# demo_dermis_chip1_package.net
KiCad netlist of a schematic drawn in Altium Designer
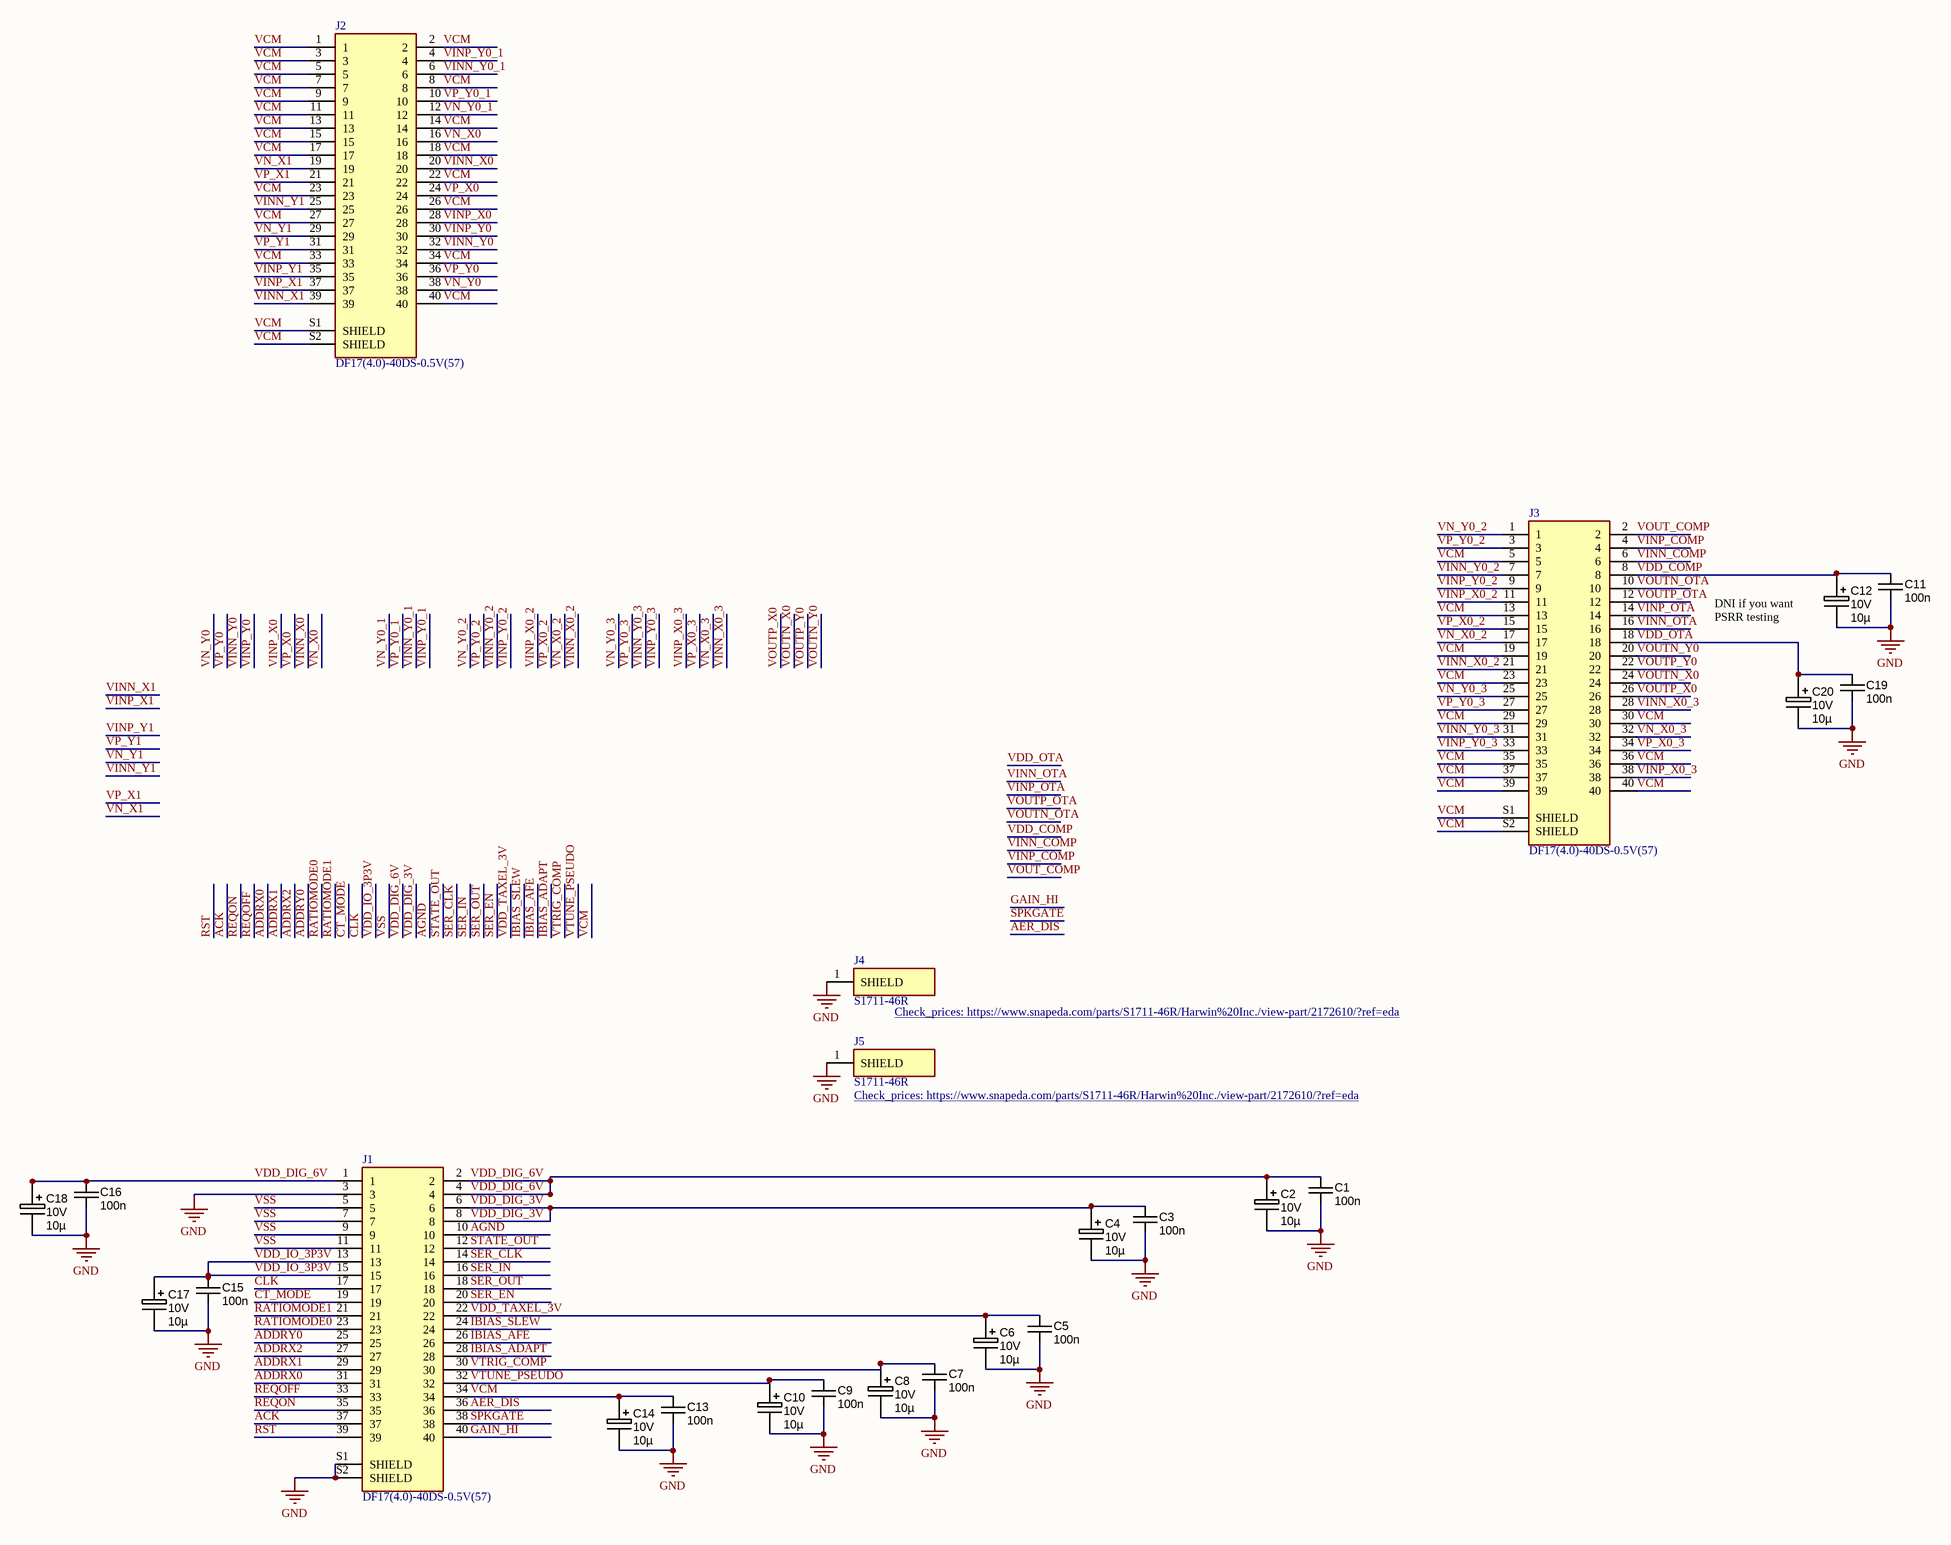
[diagram p0: demo_dermis_chip1_package.SchDoc]

(export (version "E")
  (design (tool "Eeschema 10.0.6"))
  (components
    (comp (ref "C1")
      (value "100n")
      (footprint "CAPC1608N")
      (description "Capacitor SMD Cer 100nF 10% 50V X7R 0603")
      (fields (field (name "TOLERANCE") "±10%") (field (name "Comment") "approved sub OK"))
      (libsource (lib "PBL - Capacitors") (part "CAPC_100n_0603"))
    )
    (comp (ref "C2")
      (value "10µ")
      (footprint "CAPMP2012X150USR")
      (description "Capacitor SMD Tantalum 10uF 20% 10V 0805")
      (fields (field (name "TOLERANCE") "±20%") (field (name "RATINGS") "10V"))
      (libsource (lib "PBL - Capacitors") (part "CAPT_10u_0805_10V"))
    )
    (comp (ref "C3")
      (value "100n")
      (footprint "CAPC1608N")
      (description "Capacitor SMD Cer 100nF 10% 50V X7R 0603")
      (fields (field (name "TOLERANCE") "±10%") (field (name "Comment") "approved sub OK"))
      (libsource (lib "PBL - Capacitors") (part "CAPC_100n_0603"))
    )
    (comp (ref "C4")
      (value "10µ")
      (footprint "CAPMP2012X150USR")
      (description "Capacitor SMD Tantalum 10uF 20% 10V 0805")
      (fields (field (name "TOLERANCE") "±20%") (field (name "RATINGS") "10V"))
      (libsource (lib "PBL - Capacitors") (part "CAPT_10u_0805_10V"))
    )
    (comp (ref "C5")
      (value "100n")
      (footprint "CAPC1608N")
      (description "Capacitor SMD Cer 100nF 10% 50V X7R 0603")
      (fields (field (name "TOLERANCE") "±10%") (field (name "Comment") "approved sub OK"))
      (libsource (lib "PBL - Capacitors") (part "CAPC_100n_0603"))
    )
    (comp (ref "C6")
      (value "10µ")
      (footprint "CAPMP2012X150USR")
      (description "Capacitor SMD Tantalum 10uF 20% 10V 0805")
      (fields (field (name "TOLERANCE") "±20%") (field (name "RATINGS") "10V"))
      (libsource (lib "PBL - Capacitors") (part "CAPT_10u_0805_10V"))
    )
    (comp (ref "C7")
      (value "100n")
      (footprint "CAPC1608N")
      (description "Capacitor SMD Cer 100nF 10% 50V X7R 0603")
      (fields (field (name "TOLERANCE") "±10%") (field (name "Comment") "approved sub OK"))
      (libsource (lib "PBL - Capacitors") (part "CAPC_100n_0603"))
    )
    (comp (ref "C8")
      (value "10µ")
      (footprint "CAPMP2012X150USR")
      (description "Capacitor SMD Tantalum 10uF 20% 10V 0805")
      (fields (field (name "TOLERANCE") "±20%") (field (name "RATINGS") "10V"))
      (libsource (lib "PBL - Capacitors") (part "CAPT_10u_0805_10V"))
    )
    (comp (ref "C9")
      (value "100n")
      (footprint "CAPC1608N")
      (description "Capacitor SMD Cer 100nF 10% 50V X7R 0603")
      (fields (field (name "TOLERANCE") "±10%") (field (name "Comment") "approved sub OK"))
      (libsource (lib "PBL - Capacitors") (part "CAPC_100n_0603"))
    )
    (comp (ref "C10")
      (value "10µ")
      (footprint "CAPMP2012X150USR")
      (description "Capacitor SMD Tantalum 10uF 20% 10V 0805")
      (fields (field (name "TOLERANCE") "±20%") (field (name "RATINGS") "10V"))
      (libsource (lib "PBL - Capacitors") (part "CAPT_10u_0805_10V"))
    )
    (comp (ref "C11")
      (value "100n")
      (footprint "CAPC1608N")
      (description "Capacitor SMD Cer 100nF 10% 50V X7R 0603")
      (fields (field (name "TOLERANCE") "±10%") (field (name "Comment") "approved sub OK"))
      (libsource (lib "PBL - Capacitors") (part "CAPC_100n_0603"))
    )
    (comp (ref "C12")
      (value "10µ")
      (footprint "CAPMP2012X150USR")
      (description "Capacitor SMD Tantalum 10uF 20% 10V 0805")
      (fields (field (name "TOLERANCE") "±20%") (field (name "RATINGS") "10V"))
      (libsource (lib "PBL - Capacitors") (part "CAPT_10u_0805_10V"))
    )
    (comp (ref "C13")
      (value "100n")
      (footprint "CAPC1608N")
      (description "Capacitor SMD Cer 100nF 10% 50V X7R 0603")
      (fields (field (name "TOLERANCE") "±10%") (field (name "Comment") "approved sub OK"))
      (libsource (lib "PBL - Capacitors") (part "CAPC_100n_0603"))
    )
    (comp (ref "C14")
      (value "10µ")
      (footprint "CAPMP2012X150USR")
      (description "Capacitor SMD Tantalum 10uF 20% 10V 0805")
      (fields (field (name "TOLERANCE") "±20%") (field (name "RATINGS") "10V"))
      (libsource (lib "PBL - Capacitors") (part "CAPT_10u_0805_10V"))
    )
    (comp (ref "C15")
      (value "100n")
      (footprint "CAPC1608N")
      (description "Capacitor SMD Cer 100nF 10% 50V X7R 0603")
      (fields (field (name "TOLERANCE") "±10%") (field (name "Comment") "approved sub OK"))
      (libsource (lib "PBL - Capacitors") (part "CAPC_100n_0603"))
    )
    (comp (ref "C16")
      (value "100n")
      (footprint "CAPC1608N")
      (description "Capacitor SMD Cer 100nF 10% 50V X7R 0603")
      (fields (field (name "TOLERANCE") "±10%") (field (name "Comment") "approved sub OK"))
      (libsource (lib "PBL - Capacitors") (part "CAPC_100n_0603"))
    )
    (comp (ref "C17")
      (value "10µ")
      (footprint "CAPMP2012X150USR")
      (description "Capacitor SMD Tantalum 10uF 20% 10V 0805")
      (fields (field (name "TOLERANCE") "±20%") (field (name "RATINGS") "10V"))
      (libsource (lib "PBL - Capacitors") (part "CAPT_10u_0805_10V"))
    )
    (comp (ref "C18")
      (value "10µ")
      (footprint "CAPMP2012X150USR")
      (description "Capacitor SMD Tantalum 10uF 20% 10V 0805")
      (fields (field (name "TOLERANCE") "±20%") (field (name "RATINGS") "10V"))
      (libsource (lib "PBL - Capacitors") (part "CAPT_10u_0805_10V"))
    )
    (comp (ref "C19")
      (value "100n")
      (footprint "CAPC1608N")
      (description "Capacitor SMD Cer 100nF 10% 50V X7R 0603")
      (fields (field (name "TOLERANCE") "±10%") (field (name "Comment") "approved sub OK"))
      (libsource (lib "PBL - Capacitors") (part "CAPC_100n_0603"))
    )
    (comp (ref "C20")
      (value "10µ")
      (footprint "CAPMP2012X150USR")
      (description "Capacitor SMD Tantalum 10uF 20% 10V 0805")
      (fields (field (name "TOLERANCE") "±20%") (field (name "RATINGS") "10V"))
      (libsource (lib "PBL - Capacitors") (part "CAPT_10u_0805_10V"))
    )
    (comp (ref "J1")
      (value "DF17(4.0)-40DS-0.5V(57)")
      (footprint "HRS_DF17(4.0)-40DS-0.5V(57)")
      (fields (field (name "MF") "Hirose Electric"))
      (libsource (lib "DF17(4.0)-40DS-0.5V(57)") (part "DF17(4.0)-40DS-0.5V(57)"))
    )
    (comp (ref "J2")
      (value "DF17(4.0)-40DS-0.5V(57)")
      (footprint "HRS_DF17(4.0)-40DS-0.5V(57)")
      (fields (field (name "MF") "Hirose Electric"))
      (libsource (lib "DF17(4.0)-40DS-0.5V(57)") (part "DF17(4.0)-40DS-0.5V(57)"))
    )
    (comp (ref "J3")
      (value "DF17(4.0)-40DS-0.5V(57)")
      (footprint "HRS_DF17(4.0)-40DS-0.5V(57)")
      (fields (field (name "MF") "Hirose Electric"))
      (libsource (lib "DF17(4.0)-40DS-0.5V(57)") (part "DF17(4.0)-40DS-0.5V(57)"))
    )
    (comp (ref "J4")
      (value "S1711-46R")
      (footprint "HARWIN_S1711-46R")
      (description "RFI SHIELD CLIP TIN SMD")
      (fields
        (field (name "MF") "Harwin Inc.")
        (field (name "CHECK_PRICES") "https://www.snapeda.com/parts/S1711-46R/Harwin%20Inc./view-part/2172610/?ref=eda")
      )
      (libsource (lib "S1711-46R") (part "S1711-46R"))
    )
    (comp (ref "J5")
      (value "S1711-46R")
      (footprint "HARWIN_S1711-46R")
      (description "RFI SHIELD CLIP TIN SMD")
      (fields
        (field (name "MF") "Harwin Inc.")
        (field (name "CHECK_PRICES") "https://www.snapeda.com/parts/S1711-46R/Harwin%20Inc./view-part/2172610/?ref=eda")
      )
      (libsource (lib "S1711-46R") (part "S1711-46R"))
    )
  )
  (nets
    (net (code "1") (name "/ACK") (class "Default")
      (node (ref "J1") (pin "37") (pinfunction "37_37") (pintype "passive"))
    )
    (net (code "2") (name "/ADDRX0") (class "Default")
      (node (ref "J1") (pin "31") (pinfunction "31_31") (pintype "passive"))
    )
    (net (code "3") (name "/ADDRX1") (class "Default")
      (node (ref "J1") (pin "29") (pinfunction "29_29") (pintype "passive"))
    )
    (net (code "4") (name "/ADDRX2") (class "Default")
      (node (ref "J1") (pin "27") (pinfunction "27_27") (pintype "passive"))
    )
    (net (code "5") (name "/ADDRY0") (class "Default")
      (node (ref "J1") (pin "25") (pinfunction "25_25") (pintype "passive"))
    )
    (net (code "6") (name "/AER_DIS") (class "Default")
      (node (ref "J1") (pin "36") (pinfunction "36_36") (pintype "passive"))
    )
    (net (code "7") (name "/AGND") (class "Default")
      (node (ref "J1") (pin "10") (pinfunction "10_10") (pintype "passive"))
    )
    (net (code "8") (name "/CLK") (class "Default")
      (node (ref "J1") (pin "17") (pinfunction "17_17") (pintype "passive"))
    )
    (net (code "9") (name "/CT_MODE") (class "Default")
      (node (ref "J1") (pin "19") (pinfunction "19_19") (pintype "passive"))
    )
    (net (code "10") (name "/GAIN_HI") (class "Default")
      (node (ref "J1") (pin "40") (pinfunction "40_40") (pintype "passive"))
    )
    (net (code "11") (name "/IBIAS_ADAPT") (class "Default")
      (node (ref "J1") (pin "28") (pinfunction "28_28") (pintype "passive"))
    )
    (net (code "12") (name "/IBIAS_AFE") (class "Default")
      (node (ref "J1") (pin "26") (pinfunction "26_26") (pintype "passive"))
    )
    (net (code "13") (name "/IBIAS_SLEW") (class "Default")
      (node (ref "J1") (pin "24") (pinfunction "24_24") (pintype "passive"))
    )
    (net (code "14") (name "/RATIOMODE0") (class "Default")
      (node (ref "J1") (pin "23") (pinfunction "23_23") (pintype "passive"))
    )
    (net (code "15") (name "/RATIOMODE1") (class "Default")
      (node (ref "J1") (pin "21") (pinfunction "21_21") (pintype "passive"))
    )
    (net (code "16") (name "/REQOFF") (class "Default")
      (node (ref "J1") (pin "33") (pinfunction "33_33") (pintype "passive"))
    )
    (net (code "17") (name "/REQON") (class "Default")
      (node (ref "J1") (pin "35") (pinfunction "35_35") (pintype "passive"))
    )
    (net (code "18") (name "/RST") (class "Default")
      (node (ref "J1") (pin "39") (pinfunction "39_39") (pintype "passive"))
    )
    (net (code "19") (name "/SER_CLK") (class "Default")
      (node (ref "J1") (pin "14") (pinfunction "14_14") (pintype "passive"))
    )
    (net (code "20") (name "/SER_EN") (class "Default")
      (node (ref "J1") (pin "20") (pinfunction "20_20") (pintype "passive"))
    )
    (net (code "21") (name "/SER_IN") (class "Default")
      (node (ref "J1") (pin "16") (pinfunction "16_16") (pintype "passive"))
    )
    (net (code "22") (name "/SER_OUT") (class "Default")
      (node (ref "J1") (pin "18") (pinfunction "18_18") (pintype "passive"))
    )
    (net (code "23") (name "/SPKGATE") (class "Default")
      (node (ref "J1") (pin "38") (pinfunction "38_38") (pintype "passive"))
    )
    (net (code "24") (name "/STATE_OUT") (class "Default")
      (node (ref "J1") (pin "12") (pinfunction "12_12") (pintype "passive"))
    )
    (net (code "25") (name "/VCM") (class "Default")
      (node (ref "C13") (pin "1") (pintype "passive"))
      (node (ref "C14") (pin "1") (pintype "passive"))
      (node (ref "J1") (pin "34") (pinfunction "34_34") (pintype "passive"))
      (node (ref "J2") (pin "1") (pinfunction "1_1") (pintype "passive"))
      (node (ref "J2") (pin "11") (pinfunction "11_11") (pintype "passive"))
      (node (ref "J2") (pin "13") (pinfunction "13_13") (pintype "passive"))
      (node (ref "J2") (pin "14") (pinfunction "14_14") (pintype "passive"))
      (node (ref "J2") (pin "15") (pinfunction "15_15") (pintype "passive"))
      (node (ref "J2") (pin "17") (pinfunction "17_17") (pintype "passive"))
      (node (ref "J2") (pin "18") (pinfunction "18_18") (pintype "passive"))
      (node (ref "J2") (pin "2") (pinfunction "2_2") (pintype "passive"))
      (node (ref "J2") (pin "22") (pinfunction "22_22") (pintype "passive"))
      (node (ref "J2") (pin "23") (pinfunction "23_23") (pintype "passive"))
      (node (ref "J2") (pin "26") (pinfunction "26_26") (pintype "passive"))
      (node (ref "J2") (pin "27") (pinfunction "27_27") (pintype "passive"))
      (node (ref "J2") (pin "3") (pinfunction "3_3") (pintype "passive"))
      (node (ref "J2") (pin "33") (pinfunction "33_33") (pintype "passive"))
      (node (ref "J2") (pin "34") (pinfunction "34_34") (pintype "passive"))
      (node (ref "J2") (pin "40") (pinfunction "40_40") (pintype "passive"))
      (node (ref "J2") (pin "5") (pinfunction "5_5") (pintype "passive"))
      (node (ref "J2") (pin "7") (pinfunction "7_7") (pintype "passive"))
      (node (ref "J2") (pin "8") (pinfunction "8_8") (pintype "passive"))
      (node (ref "J2") (pin "9") (pinfunction "9_9") (pintype "passive"))
      (node (ref "J2") (pin "S1") (pinfunction "SHIELD_S1") (pintype "passive"))
      (node (ref "J2") (pin "S2") (pinfunction "SHIELD_S2") (pintype "passive"))
      (node (ref "J3") (pin "13") (pinfunction "13_13") (pintype "passive"))
      (node (ref "J3") (pin "19") (pinfunction "19_19") (pintype "passive"))
      (node (ref "J3") (pin "23") (pinfunction "23_23") (pintype "passive"))
      (node (ref "J3") (pin "29") (pinfunction "29_29") (pintype "passive"))
      (node (ref "J3") (pin "30") (pinfunction "30_30") (pintype "passive"))
      (node (ref "J3") (pin "35") (pinfunction "35_35") (pintype "passive"))
      (node (ref "J3") (pin "36") (pinfunction "36_36") (pintype "passive"))
      (node (ref "J3") (pin "37") (pinfunction "37_37") (pintype "passive"))
      (node (ref "J3") (pin "39") (pinfunction "39_39") (pintype "passive"))
      (node (ref "J3") (pin "40") (pinfunction "40_40") (pintype "passive"))
      (node (ref "J3") (pin "5") (pinfunction "5_5") (pintype "passive"))
      (node (ref "J3") (pin "S1") (pinfunction "SHIELD_S1") (pintype "passive"))
      (node (ref "J3") (pin "S2") (pinfunction "SHIELD_S2") (pintype "passive"))
    )
    (net (code "26") (name "/VDD_COMP") (class "Default")
      (node (ref "C11") (pin "1") (pintype "passive"))
      (node (ref "C12") (pin "1") (pintype "passive"))
      (node (ref "J3") (pin "8") (pinfunction "8_8") (pintype "passive"))
    )
    (net (code "27") (name "/VDD_DIG_3V") (class "Default")
      (node (ref "C3") (pin "1") (pintype "passive"))
      (node (ref "C4") (pin "1") (pintype "passive"))
      (node (ref "J1") (pin "6") (pinfunction "6_6") (pintype "passive"))
      (node (ref "J1") (pin "8") (pinfunction "8_8") (pintype "passive"))
    )
    (net (code "28") (name "/VDD_DIG_6V") (class "Default")
      (node (ref "C1") (pin "1") (pintype "passive"))
      (node (ref "C16") (pin "1") (pintype "passive"))
      (node (ref "C18") (pin "1") (pintype "passive"))
      (node (ref "C2") (pin "1") (pintype "passive"))
      (node (ref "J1") (pin "1") (pinfunction "1_1") (pintype "passive"))
      (node (ref "J1") (pin "2") (pinfunction "2_2") (pintype "passive"))
      (node (ref "J1") (pin "4") (pinfunction "4_4") (pintype "passive"))
    )
    (net (code "29") (name "/VDD_IO_3P3V") (class "Default")
      (node (ref "C15") (pin "1") (pintype "passive"))
      (node (ref "C17") (pin "1") (pintype "passive"))
      (node (ref "J1") (pin "13") (pinfunction "13_13") (pintype "passive"))
      (node (ref "J1") (pin "15") (pinfunction "15_15") (pintype "passive"))
    )
    (net (code "30") (name "/VDD_OTA") (class "Default")
      (node (ref "C19") (pin "1") (pintype "passive"))
      (node (ref "C20") (pin "1") (pintype "passive"))
      (node (ref "J3") (pin "18") (pinfunction "18_18") (pintype "passive"))
    )
    (net (code "31") (name "/VDD_TAXEL_3V") (class "Default")
      (node (ref "C5") (pin "1") (pintype "passive"))
      (node (ref "C6") (pin "1") (pintype "passive"))
      (node (ref "J1") (pin "22") (pinfunction "22_22") (pintype "passive"))
    )
    (net (code "32") (name "/VINN_COMP") (class "Default")
      (node (ref "J3") (pin "6") (pinfunction "6_6") (pintype "passive"))
    )
    (net (code "33") (name "/VINN_OTA") (class "Default")
      (node (ref "J3") (pin "16") (pinfunction "16_16") (pintype "passive"))
    )
    (net (code "34") (name "/VINN_X0") (class "Default")
      (node (ref "J2") (pin "20") (pinfunction "20_20") (pintype "passive"))
    )
    (net (code "35") (name "/VINN_X0_2") (class "Default")
      (node (ref "J3") (pin "21") (pinfunction "21_21") (pintype "passive"))
    )
    (net (code "36") (name "/VINN_X0_3") (class "Default")
      (node (ref "J3") (pin "28") (pinfunction "28_28") (pintype "passive"))
    )
    (net (code "37") (name "/VINN_X1") (class "Default")
      (node (ref "J2") (pin "39") (pinfunction "39_39") (pintype "passive"))
    )
    (net (code "38") (name "/VINN_Y0") (class "Default")
      (node (ref "J2") (pin "32") (pinfunction "32_32") (pintype "passive"))
    )
    (net (code "39") (name "/VINN_Y0_1") (class "Default")
      (node (ref "J2") (pin "6") (pinfunction "6_6") (pintype "passive"))
    )
    (net (code "40") (name "/VINN_Y0_2") (class "Default")
      (node (ref "J3") (pin "7") (pinfunction "7_7") (pintype "passive"))
    )
    (net (code "41") (name "/VINN_Y0_3") (class "Default")
      (node (ref "J3") (pin "31") (pinfunction "31_31") (pintype "passive"))
    )
    (net (code "42") (name "/VINN_Y1") (class "Default")
      (node (ref "J2") (pin "25") (pinfunction "25_25") (pintype "passive"))
    )
    (net (code "43") (name "/VINP_COMP") (class "Default")
      (node (ref "J3") (pin "4") (pinfunction "4_4") (pintype "passive"))
    )
    (net (code "44") (name "/VINP_OTA") (class "Default")
      (node (ref "J3") (pin "14") (pinfunction "14_14") (pintype "passive"))
    )
    (net (code "45") (name "/VINP_X0") (class "Default")
      (node (ref "J2") (pin "28") (pinfunction "28_28") (pintype "passive"))
    )
    (net (code "46") (name "/VINP_X0_2") (class "Default")
      (node (ref "J3") (pin "11") (pinfunction "11_11") (pintype "passive"))
    )
    (net (code "47") (name "/VINP_X0_3") (class "Default")
      (node (ref "J3") (pin "38") (pinfunction "38_38") (pintype "passive"))
    )
    (net (code "48") (name "/VINP_X1") (class "Default")
      (node (ref "J2") (pin "37") (pinfunction "37_37") (pintype "passive"))
    )
    (net (code "49") (name "/VINP_Y0") (class "Default")
      (node (ref "J2") (pin "30") (pinfunction "30_30") (pintype "passive"))
    )
    (net (code "50") (name "/VINP_Y0_1") (class "Default")
      (node (ref "J2") (pin "4") (pinfunction "4_4") (pintype "passive"))
    )
    (net (code "51") (name "/VINP_Y0_2") (class "Default")
      (node (ref "J3") (pin "9") (pinfunction "9_9") (pintype "passive"))
    )
    (net (code "52") (name "/VINP_Y0_3") (class "Default")
      (node (ref "J3") (pin "33") (pinfunction "33_33") (pintype "passive"))
    )
    (net (code "53") (name "/VINP_Y1") (class "Default")
      (node (ref "J2") (pin "35") (pinfunction "35_35") (pintype "passive"))
    )
    (net (code "54") (name "/VN_X0") (class "Default")
      (node (ref "J2") (pin "16") (pinfunction "16_16") (pintype "passive"))
    )
    (net (code "55") (name "/VN_X0_2") (class "Default")
      (node (ref "J3") (pin "17") (pinfunction "17_17") (pintype "passive"))
    )
    (net (code "56") (name "/VN_X0_3") (class "Default")
      (node (ref "J3") (pin "32") (pinfunction "32_32") (pintype "passive"))
    )
    (net (code "57") (name "/VN_X1") (class "Default")
      (node (ref "J2") (pin "19") (pinfunction "19_19") (pintype "passive"))
    )
    (net (code "58") (name "/VN_Y0") (class "Default")
      (node (ref "J2") (pin "38") (pinfunction "38_38") (pintype "passive"))
    )
    (net (code "59") (name "/VN_Y0_1") (class "Default")
      (node (ref "J2") (pin "12") (pinfunction "12_12") (pintype "passive"))
    )
    (net (code "60") (name "/VN_Y0_2") (class "Default")
      (node (ref "J3") (pin "1") (pinfunction "1_1") (pintype "passive"))
    )
    (net (code "61") (name "/VN_Y0_3") (class "Default")
      (node (ref "J3") (pin "25") (pinfunction "25_25") (pintype "passive"))
    )
    (net (code "62") (name "/VN_Y1") (class "Default")
      (node (ref "J2") (pin "29") (pinfunction "29_29") (pintype "passive"))
    )
    (net (code "63") (name "/VOUTN_OTA") (class "Default")
      (node (ref "J3") (pin "10") (pinfunction "10_10") (pintype "passive"))
    )
    (net (code "64") (name "/VOUTN_X0") (class "Default")
      (node (ref "J3") (pin "24") (pinfunction "24_24") (pintype "passive"))
    )
    (net (code "65") (name "/VOUTN_Y0") (class "Default")
      (node (ref "J3") (pin "20") (pinfunction "20_20") (pintype "passive"))
    )
    (net (code "66") (name "/VOUTP_OTA") (class "Default")
      (node (ref "J3") (pin "12") (pinfunction "12_12") (pintype "passive"))
    )
    (net (code "67") (name "/VOUTP_X0") (class "Default")
      (node (ref "J3") (pin "26") (pinfunction "26_26") (pintype "passive"))
    )
    (net (code "68") (name "/VOUTP_Y0") (class "Default")
      (node (ref "J3") (pin "22") (pinfunction "22_22") (pintype "passive"))
    )
    (net (code "69") (name "/VOUT_COMP") (class "Default")
      (node (ref "J3") (pin "2") (pinfunction "2_2") (pintype "passive"))
    )
    (net (code "70") (name "/VP_X0") (class "Default")
      (node (ref "J2") (pin "24") (pinfunction "24_24") (pintype "passive"))
    )
    (net (code "71") (name "/VP_X0_2") (class "Default")
      (node (ref "J3") (pin "15") (pinfunction "15_15") (pintype "passive"))
    )
    (net (code "72") (name "/VP_X0_3") (class "Default")
      (node (ref "J3") (pin "34") (pinfunction "34_34") (pintype "passive"))
    )
    (net (code "73") (name "/VP_X1") (class "Default")
      (node (ref "J2") (pin "21") (pinfunction "21_21") (pintype "passive"))
    )
    (net (code "74") (name "/VP_Y0") (class "Default")
      (node (ref "J2") (pin "36") (pinfunction "36_36") (pintype "passive"))
    )
    (net (code "75") (name "/VP_Y0_1") (class "Default")
      (node (ref "J2") (pin "10") (pinfunction "10_10") (pintype "passive"))
    )
    (net (code "76") (name "/VP_Y0_2") (class "Default")
      (node (ref "J3") (pin "3") (pinfunction "3_3") (pintype "passive"))
    )
    (net (code "77") (name "/VP_Y0_3") (class "Default")
      (node (ref "J3") (pin "27") (pinfunction "27_27") (pintype "passive"))
    )
    (net (code "78") (name "/VP_Y1") (class "Default")
      (node (ref "J2") (pin "31") (pinfunction "31_31") (pintype "passive"))
    )
    (net (code "79") (name "/VSS") (class "Default")
      (node (ref "J1") (pin "11") (pinfunction "11_11") (pintype "passive"))
      (node (ref "J1") (pin "5") (pinfunction "5_5") (pintype "passive"))
      (node (ref "J1") (pin "7") (pinfunction "7_7") (pintype "passive"))
      (node (ref "J1") (pin "9") (pinfunction "9_9") (pintype "passive"))
    )
    (net (code "80") (name "/VTRIG_COMP") (class "Default")
      (node (ref "C7") (pin "1") (pintype "passive"))
      (node (ref "C8") (pin "1") (pintype "passive"))
      (node (ref "J1") (pin "30") (pinfunction "30_30") (pintype "passive"))
    )
    (net (code "81") (name "/VTUNE_PSEUDO") (class "Default")
      (node (ref "C10") (pin "1") (pintype "passive"))
      (node (ref "C9") (pin "1") (pintype "passive"))
      (node (ref "J1") (pin "32") (pinfunction "32_32") (pintype "passive"))
    )
    (net (code "82") (name "GND") (class "Default")
      (node (ref "C1") (pin "2") (pintype "passive"))
      (node (ref "C10") (pin "2") (pintype "passive"))
      (node (ref "C11") (pin "2") (pintype "passive"))
      (node (ref "C12") (pin "2") (pintype "passive"))
      (node (ref "C13") (pin "2") (pintype "passive"))
      (node (ref "C14") (pin "2") (pintype "passive"))
      (node (ref "C15") (pin "2") (pintype "passive"))
      (node (ref "C16") (pin "2") (pintype "passive"))
      (node (ref "C17") (pin "2") (pintype "passive"))
      (node (ref "C18") (pin "2") (pintype "passive"))
      (node (ref "C19") (pin "2") (pintype "passive"))
      (node (ref "C2") (pin "2") (pintype "passive"))
      (node (ref "C20") (pin "2") (pintype "passive"))
      (node (ref "C3") (pin "2") (pintype "passive"))
      (node (ref "C4") (pin "2") (pintype "passive"))
      (node (ref "C5") (pin "2") (pintype "passive"))
      (node (ref "C6") (pin "2") (pintype "passive"))
      (node (ref "C7") (pin "2") (pintype "passive"))
      (node (ref "C8") (pin "2") (pintype "passive"))
      (node (ref "C9") (pin "2") (pintype "passive"))
      (node (ref "J1") (pin "3") (pinfunction "3_3") (pintype "passive"))
      (node (ref "J1") (pin "S1") (pinfunction "SHIELD_S1") (pintype "passive"))
      (node (ref "J1") (pin "S2") (pinfunction "SHIELD_S2") (pintype "passive"))
      (node (ref "J4") (pin "1") (pinfunction "SHIELD_1") (pintype "passive"))
      (node (ref "J5") (pin "1") (pinfunction "SHIELD_1") (pintype "passive"))
    )
  )
)
